# RF-antenna_B.net
KiCad netlist of a schematic drawn in EAGLE
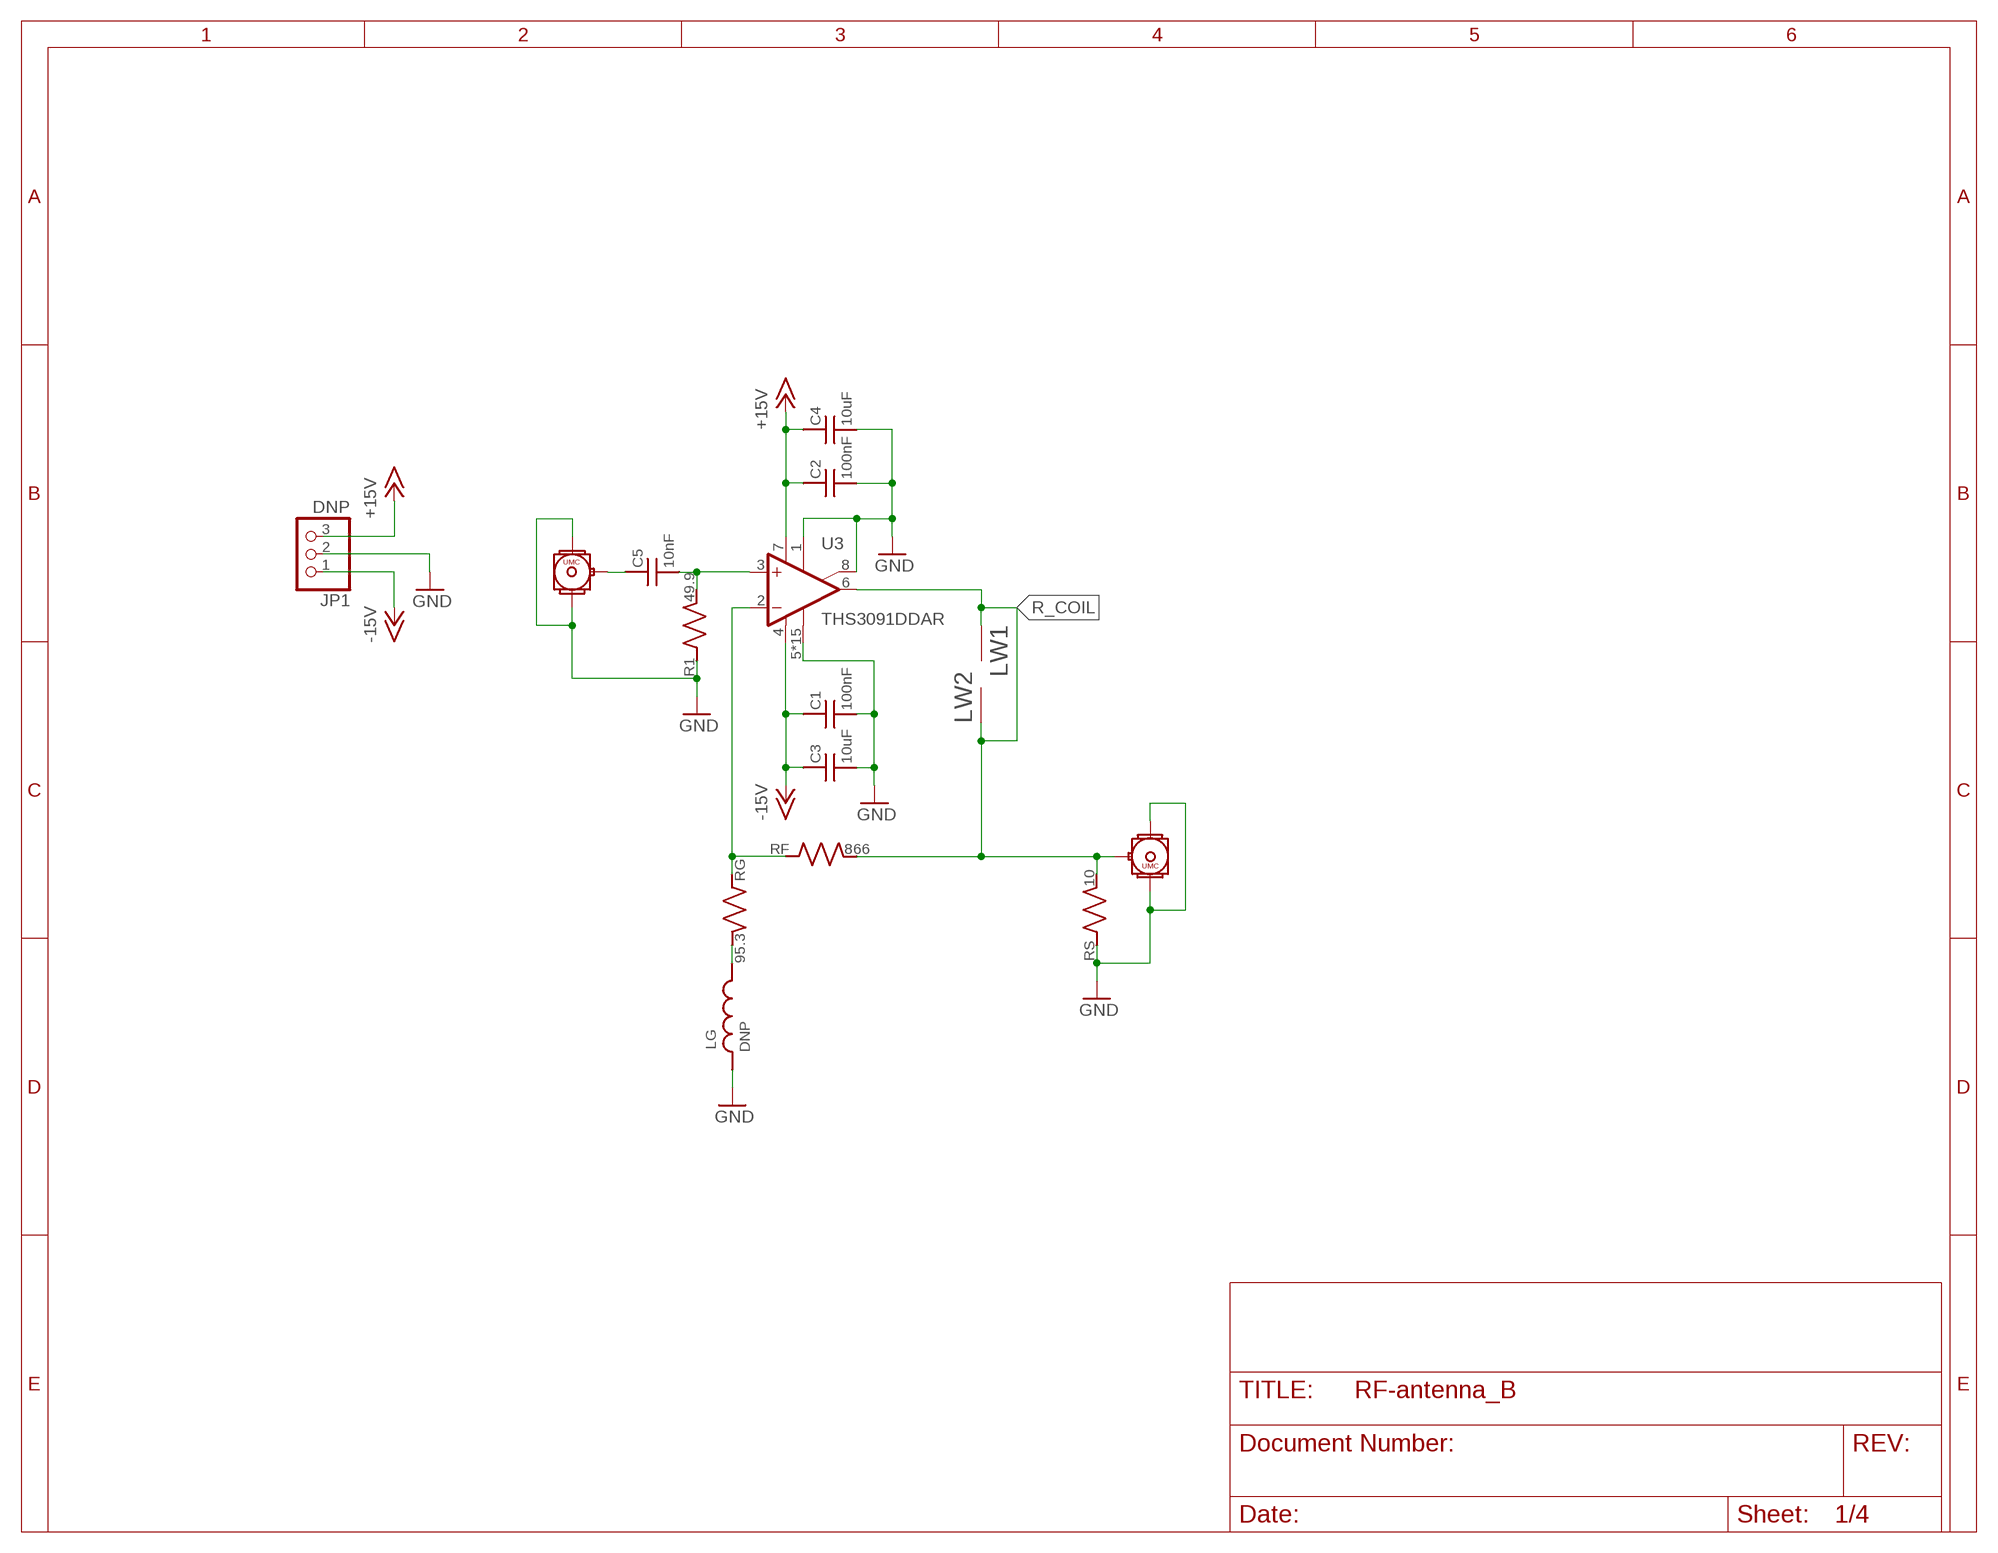
[diagram p0: schematic, sheet 1]
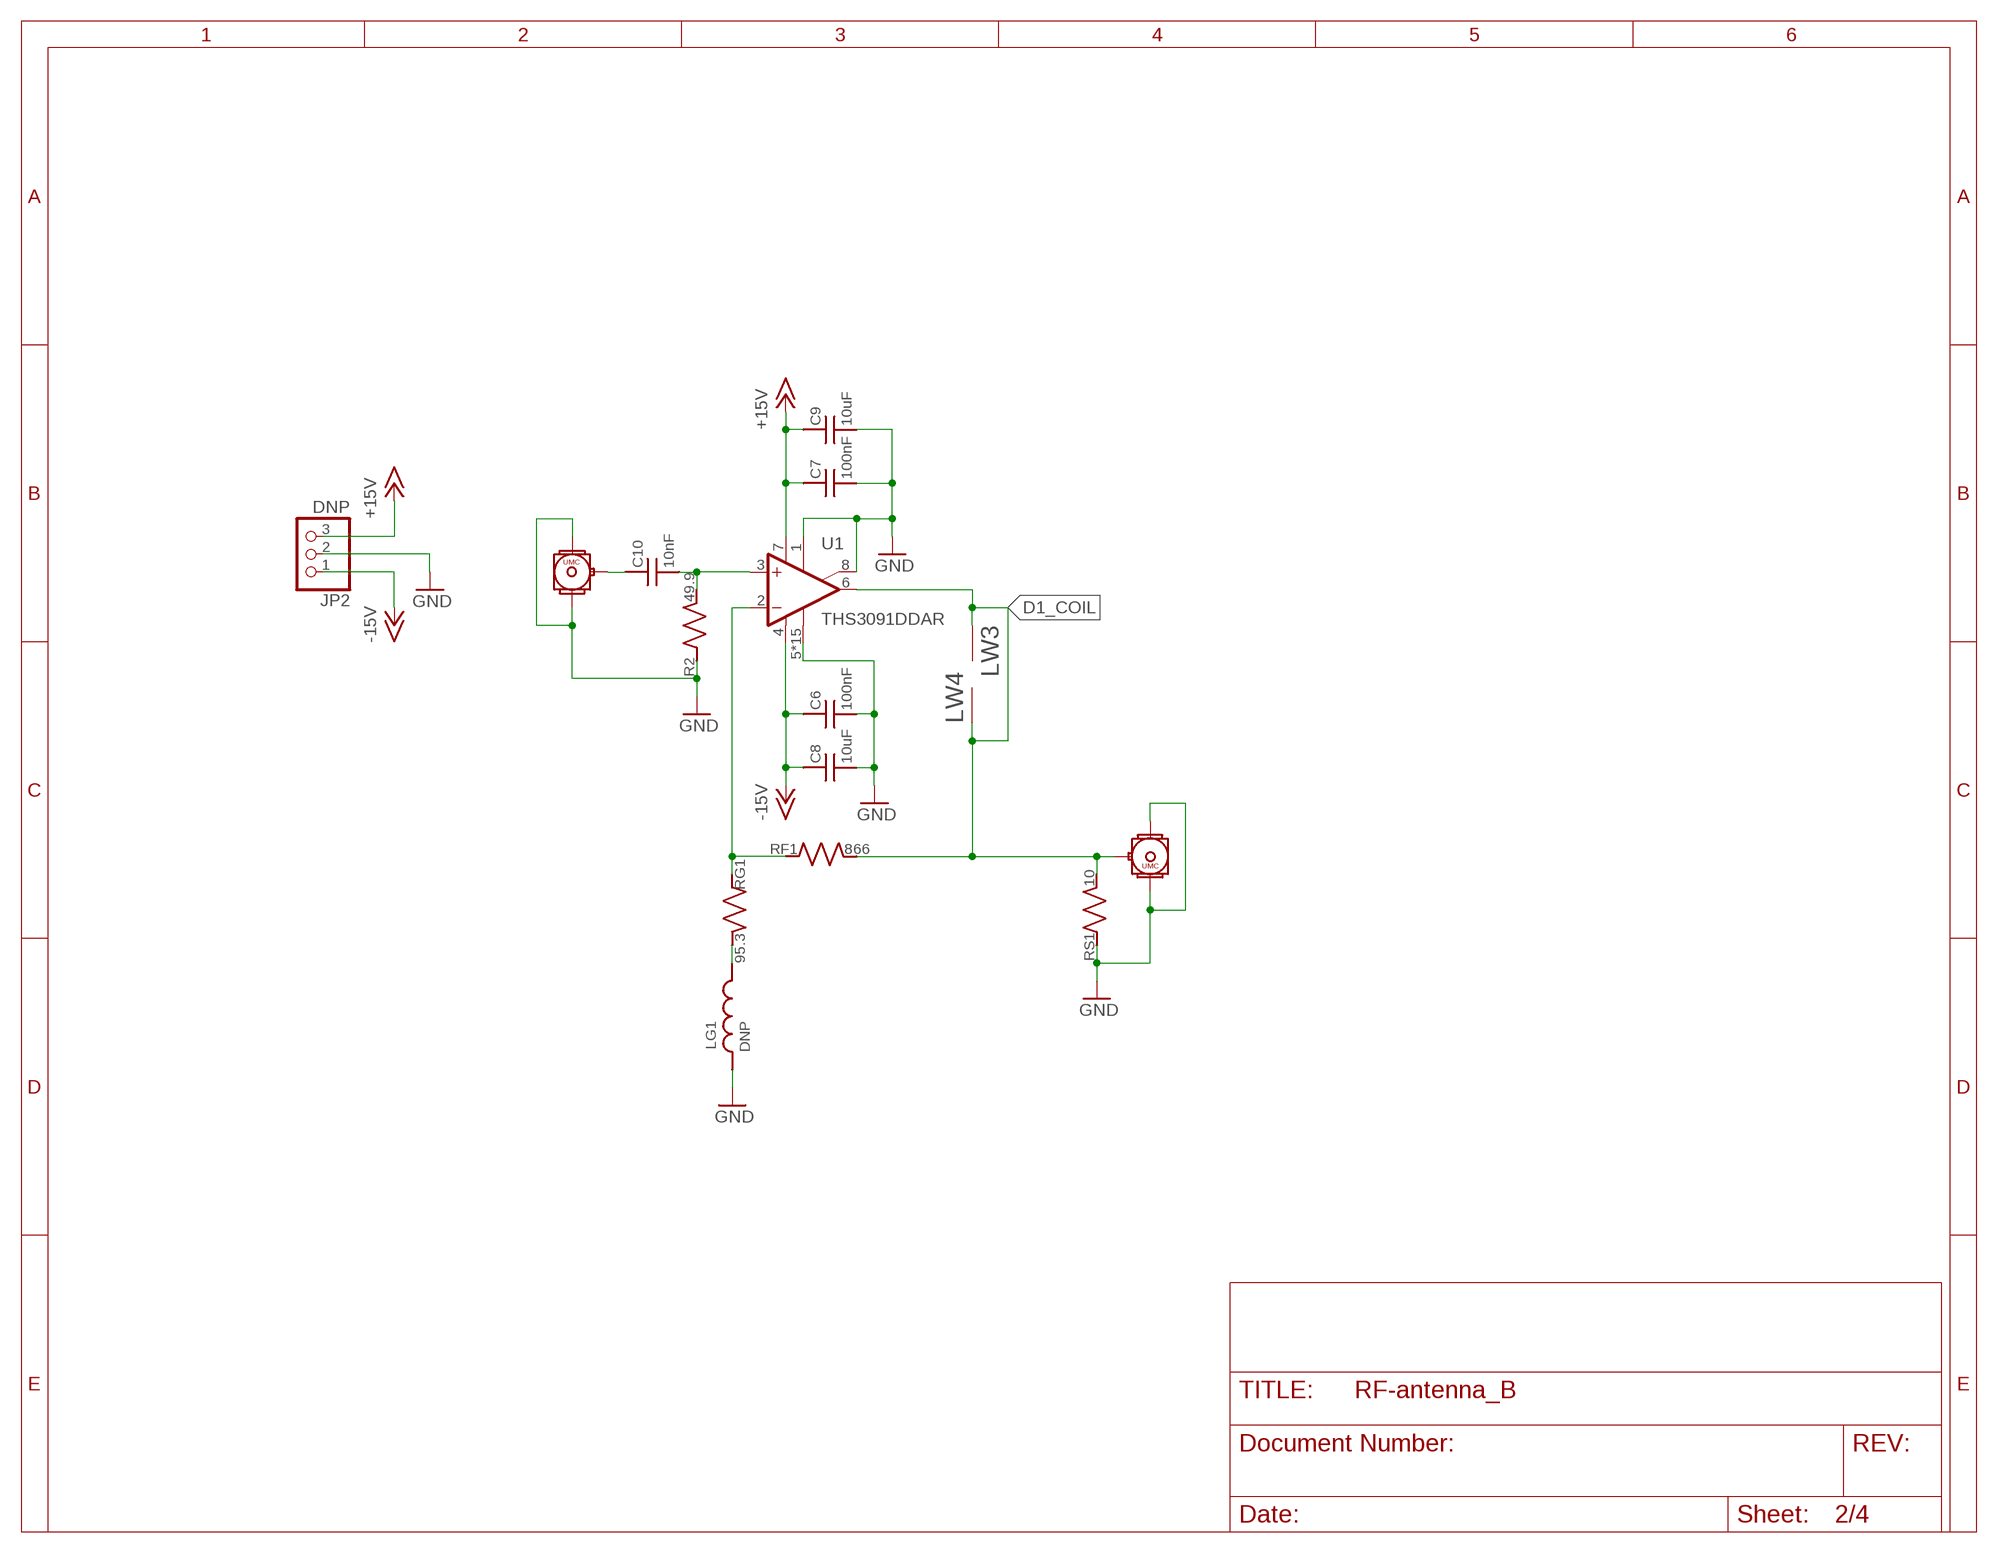
[diagram p1: schematic, sheet 2]
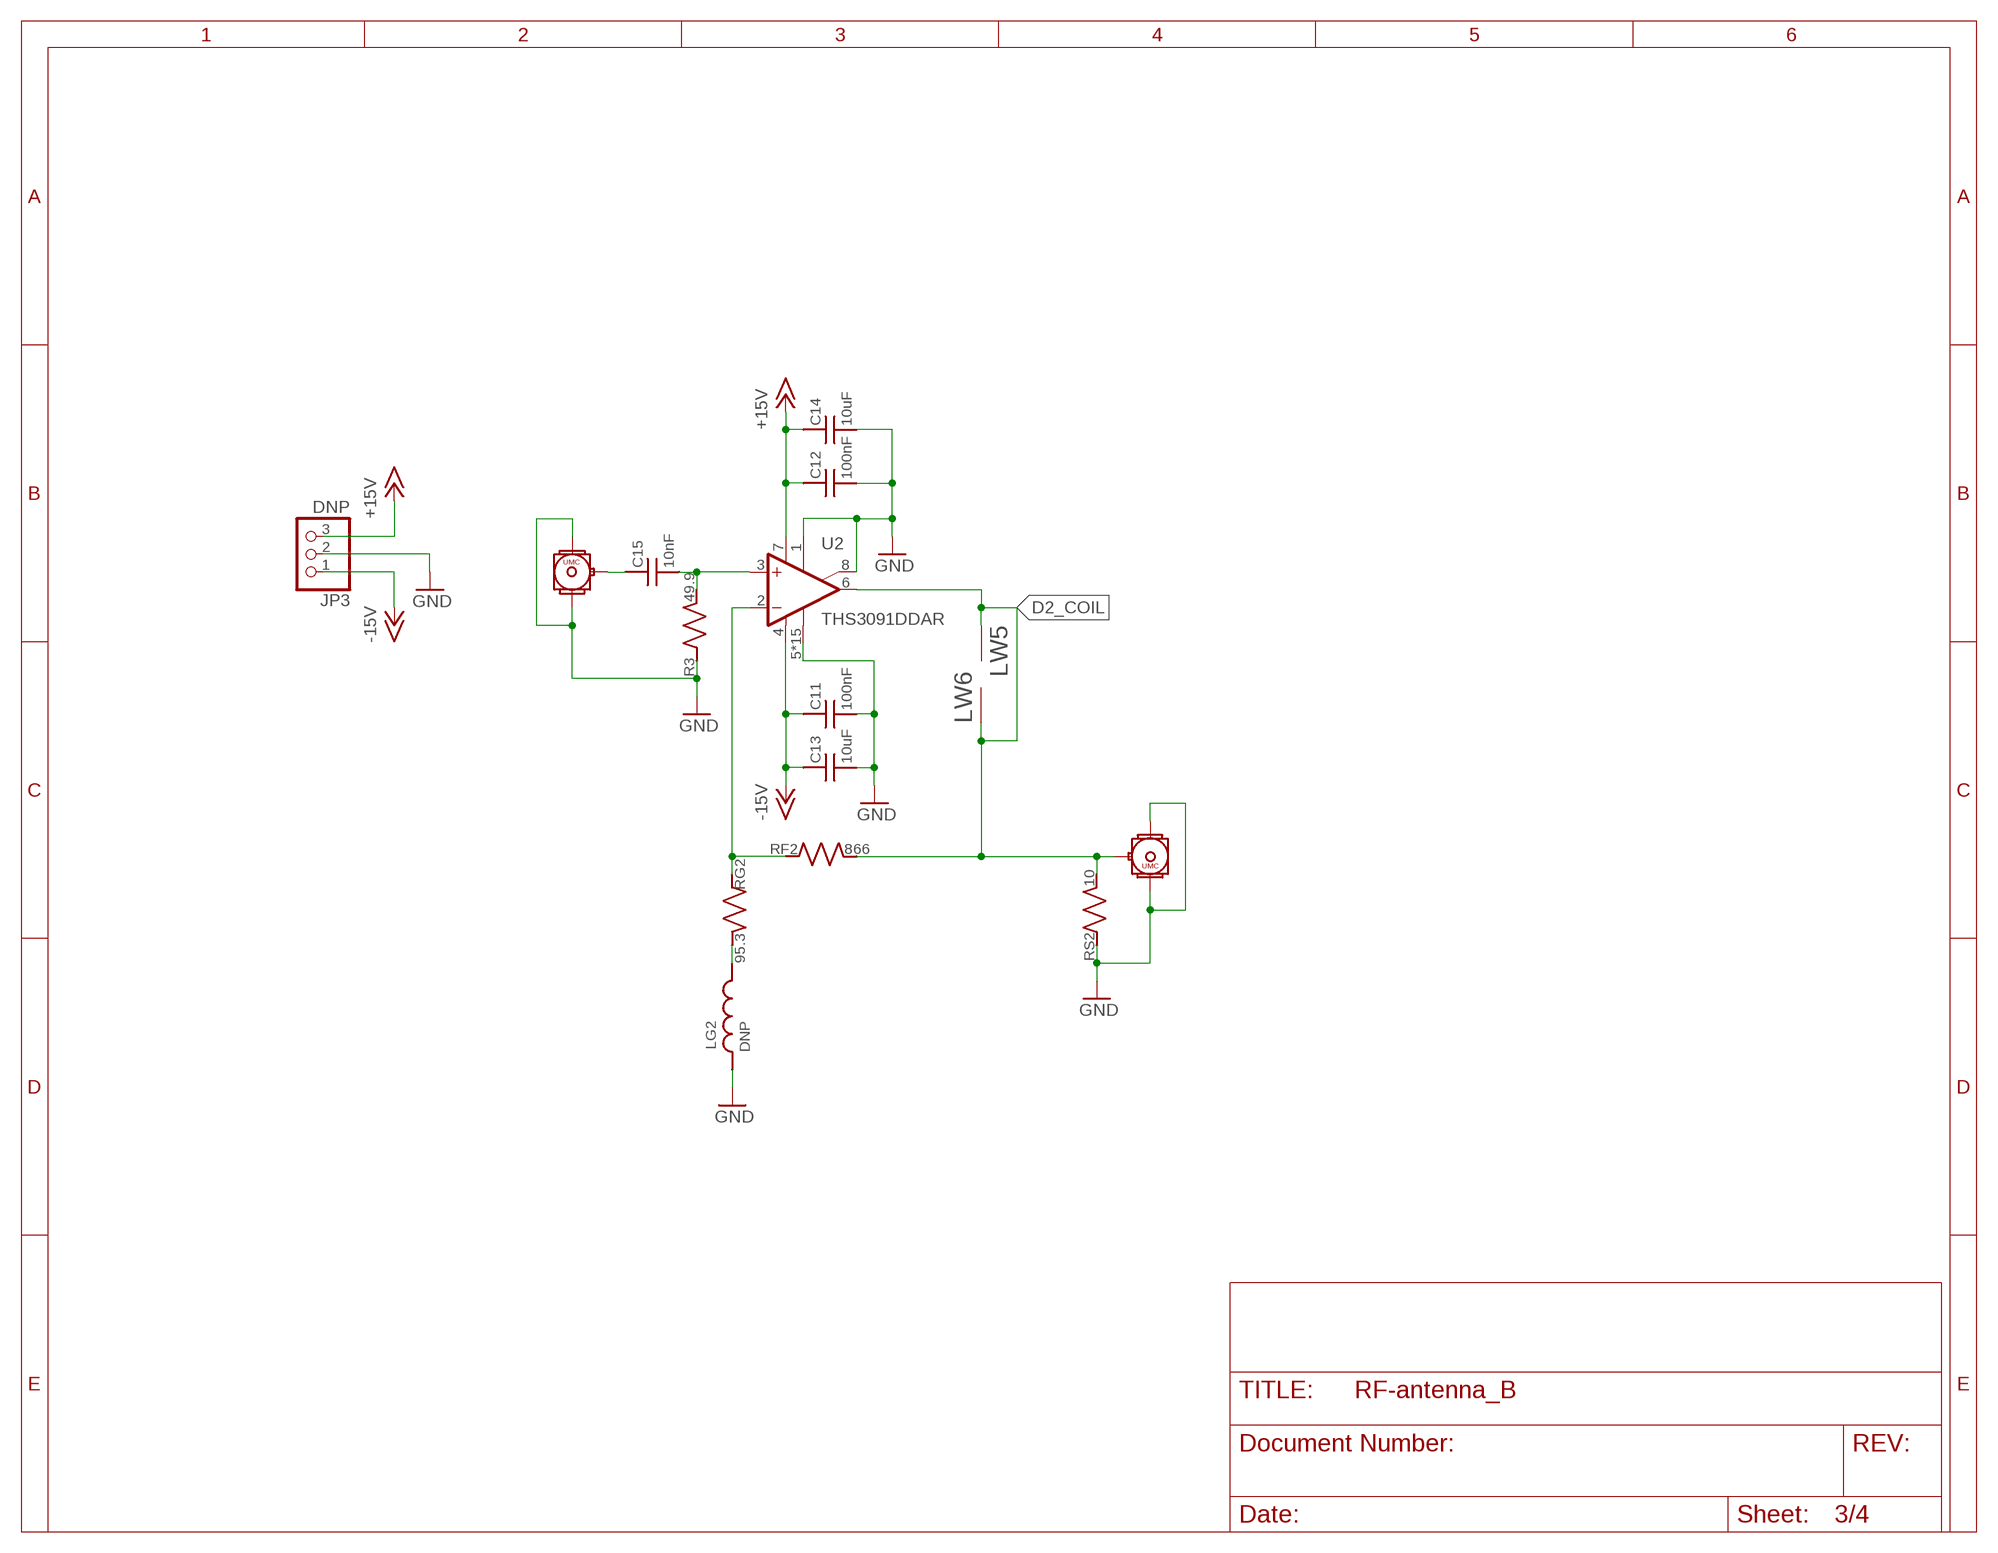
[diagram p2: schematic, sheet 3]
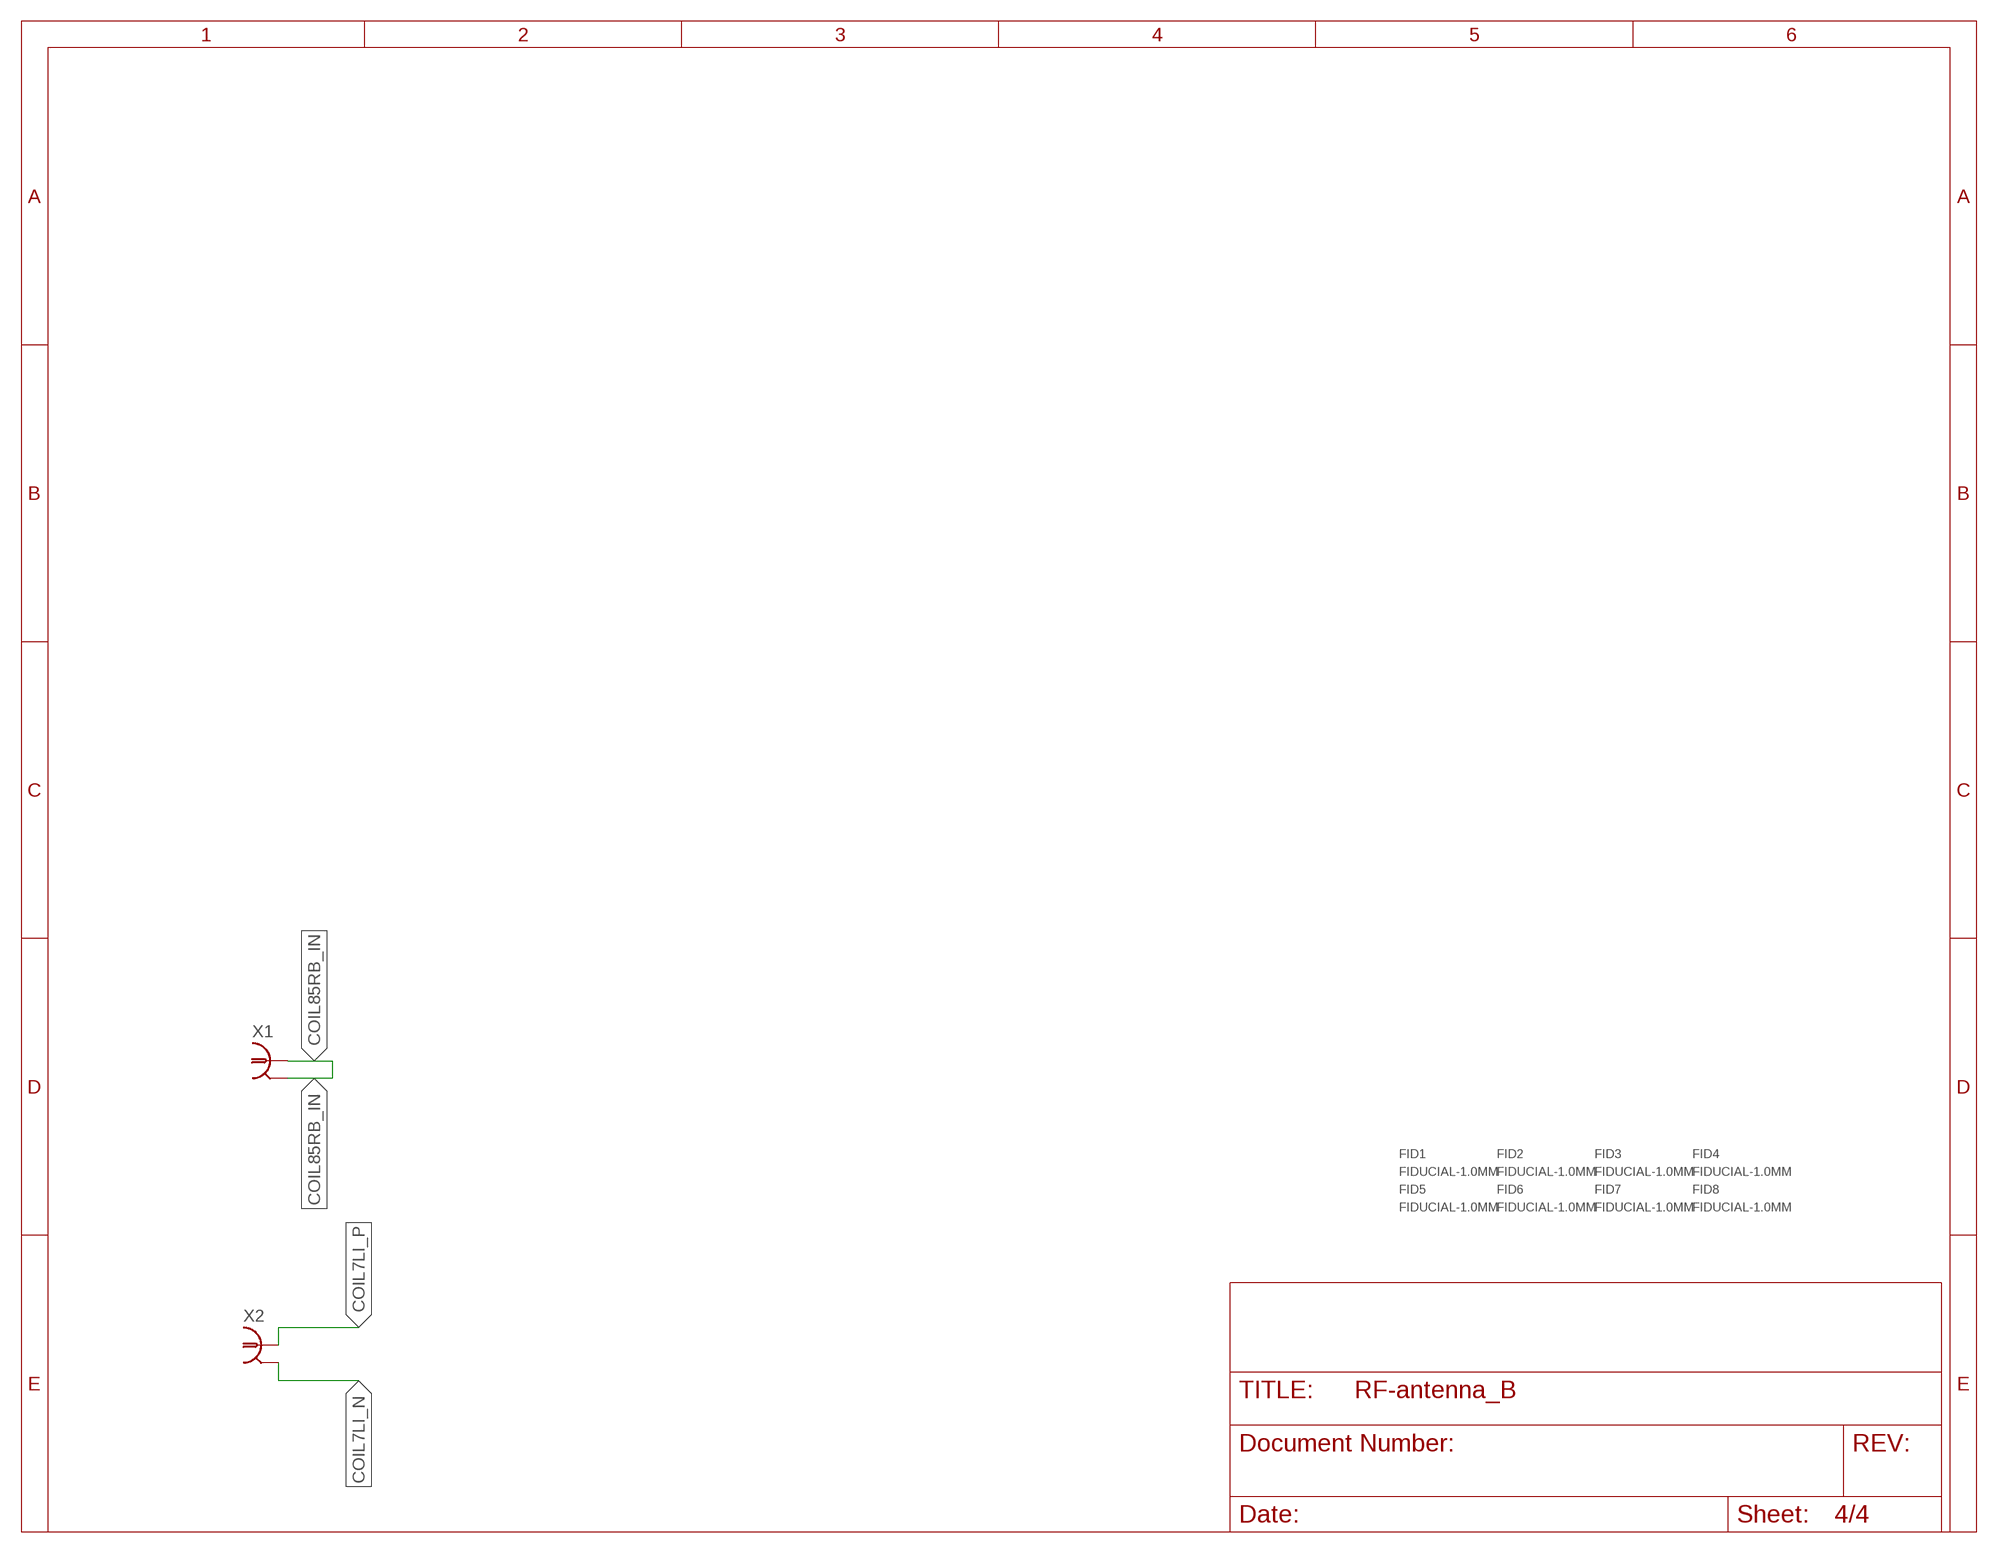
[diagram p3: schematic, sheet 4]

(export (version "E")
  (design (tool "Eeschema 10.0.6"))
  (components
    (comp (ref "C6")
      (value "100nF")
      (footprint "eagle-import:C_MLCC_0603")
      (fields (field (name "PARTNO") "06035C104K4Z2A"))
      (libsource (lib "eagle-import") (part "C_MLCC_SMDCMLCC_0603"))
    )
    (comp (ref "C7")
      (value "100nF")
      (footprint "eagle-import:C_MLCC_0603")
      (fields (field (name "PARTNO") "06035C104K4Z2A"))
      (libsource (lib "eagle-import") (part "C_MLCC_SMDCMLCC_0603"))
    )
    (comp (ref "C8")
      (value "10uF")
      (footprint "eagle-import:C_MLCC_1206")
      (fields (field (name "PARTNO") "C3216X5R1H106K160AB"))
      (libsource (lib "eagle-import") (part "C_MLCC_SMDCMLCC_1206"))
    )
    (comp (ref "C9")
      (value "10uF")
      (footprint "eagle-import:C_MLCC_1206")
      (fields (field (name "PARTNO") "C3216X5R1H106K160AB"))
      (libsource (lib "eagle-import") (part "C_MLCC_SMDCMLCC_1206"))
    )
    (comp (ref "C10")
      (value "10nF")
      (footprint "eagle-import:C_MLCC_0402")
      (fields (field (name "PARTNO") "CL05B103KB5NNNC"))
      (libsource (lib "eagle-import") (part "C_MLCC_SMDCMLCC_0402"))
    )
    (comp (ref "CON3")
      (value "UMC_CONNECTORREGULAR")
      (footprint "eagle-import:UMC_CONNECTOR")
      (fields (field (name "PARTNO") "1909763-1"))
      (libsource (lib "eagle-import") (part "UMC_CONNECTORREGULAR"))
    )
    (comp (ref "CON4")
      (value "UMC_CONNECTORREGULAR")
      (footprint "eagle-import:UMC_CONNECTOR")
      (fields (field (name "PARTNO") "1909763-1"))
      (libsource (lib "eagle-import") (part "UMC_CONNECTORREGULAR"))
    )
    (comp (ref "JP2")
      (value "DNP")
      (footprint "eagle-import:1X03")
      (fields (field (name "PARTNO") "640456-3"))
      (libsource (lib "eagle-import") (part "PINHD-1X3"))
    )
    (comp (ref "LG1")
      (value "DNP")
      (footprint "eagle-import:1008")
      (libsource (lib "eagle-import") (part "L_FERRITE_SMD_1008"))
    )
    (comp (ref "LW3")
      (value "LITZ_TERM")
      (footprint "eagle-import:LITZ_100MHZ")
      (libsource (lib "eagle-import") (part "LITZ_TERM"))
    )
    (comp (ref "LW4")
      (value "LITZ_TERM")
      (footprint "eagle-import:LITZ_100MHZ")
      (libsource (lib "eagle-import") (part "LITZ_TERM"))
    )
    (comp (ref "R2")
      (value "49.9")
      (footprint "eagle-import:R_0402")
      (fields (field (name "PARTNO") "ERA-2AEB49R9X"))
      (libsource (lib "eagle-import") (part "R_SMDR0402"))
    )
    (comp (ref "RF1")
      (value "866")
      (footprint "eagle-import:R_0603")
      (fields (field (name "PARTNO") "ERA-3AEB8660V"))
      (libsource (lib "eagle-import") (part "R_SMDR0603"))
    )
    (comp (ref "RG1")
      (value "95.3")
      (footprint "eagle-import:R_0402")
      (fields (field (name "PARTNO") "ERA-2AEB95R3X"))
      (libsource (lib "eagle-import") (part "R_SMDR0402"))
    )
    (comp (ref "RS1")
      (value "10")
      (footprint "eagle-import:R_1206")
      (fields (field (name "PARTNO") "PHP01206E10R0BST5"))
      (libsource (lib "eagle-import") (part "R_SMDR1206"))
    )
    (comp (ref "U1")
      (value "THS3091DDAR")
      (footprint "eagle-import:DDA8_2P28X2P28")
      (fields (field (name "MANUFACTURER") "Texas Instruments"))
      (libsource (lib "eagle-import") (part "THS3091DDAR"))
    )
    (comp (ref "C11")
      (value "100nF")
      (footprint "eagle-import:C_MLCC_0603")
      (fields (field (name "PARTNO") "06035C104K4Z2A"))
      (libsource (lib "eagle-import") (part "C_MLCC_SMDCMLCC_0603"))
    )
    (comp (ref "C12")
      (value "100nF")
      (footprint "eagle-import:C_MLCC_0603")
      (fields (field (name "PARTNO") "06035C104K4Z2A"))
      (libsource (lib "eagle-import") (part "C_MLCC_SMDCMLCC_0603"))
    )
    (comp (ref "C13")
      (value "10uF")
      (footprint "eagle-import:C_MLCC_1206")
      (fields (field (name "PARTNO") "C3216X5R1H106K160AB"))
      (libsource (lib "eagle-import") (part "C_MLCC_SMDCMLCC_1206"))
    )
    (comp (ref "C14")
      (value "10uF")
      (footprint "eagle-import:C_MLCC_1206")
      (fields (field (name "PARTNO") "C3216X5R1H106K160AB"))
      (libsource (lib "eagle-import") (part "C_MLCC_SMDCMLCC_1206"))
    )
    (comp (ref "C15")
      (value "10nF")
      (footprint "eagle-import:C_MLCC_0402")
      (fields (field (name "PARTNO") "CL05B103KB5NNNC"))
      (libsource (lib "eagle-import") (part "C_MLCC_SMDCMLCC_0402"))
    )
    (comp (ref "CON5")
      (value "UMC_CONNECTORREGULAR")
      (footprint "eagle-import:UMC_CONNECTOR")
      (fields (field (name "PARTNO") "1909763-1"))
      (libsource (lib "eagle-import") (part "UMC_CONNECTORREGULAR"))
    )
    (comp (ref "CON6")
      (value "UMC_CONNECTORREGULAR")
      (footprint "eagle-import:UMC_CONNECTOR")
      (fields (field (name "PARTNO") "1909763-1"))
      (libsource (lib "eagle-import") (part "UMC_CONNECTORREGULAR"))
    )
    (comp (ref "JP3")
      (value "DNP")
      (footprint "eagle-import:1X03")
      (fields (field (name "PARTNO") "640456-3"))
      (libsource (lib "eagle-import") (part "PINHD-1X3"))
    )
    (comp (ref "LG2")
      (value "DNP")
      (footprint "eagle-import:1008")
      (libsource (lib "eagle-import") (part "L_FERRITE_SMD_1008"))
    )
    (comp (ref "LW5")
      (value "LITZ_TERM")
      (footprint "eagle-import:LITZ_100MHZ")
      (libsource (lib "eagle-import") (part "LITZ_TERM"))
    )
    (comp (ref "LW6")
      (value "LITZ_TERM")
      (footprint "eagle-import:LITZ_100MHZ")
      (libsource (lib "eagle-import") (part "LITZ_TERM"))
    )
    (comp (ref "R3")
      (value "49.9")
      (footprint "eagle-import:R_0402")
      (fields (field (name "PARTNO") "ERA-2AEB49R9X"))
      (libsource (lib "eagle-import") (part "R_SMDR0402"))
    )
    (comp (ref "RF2")
      (value "866")
      (footprint "eagle-import:R_0603")
      (fields (field (name "PARTNO") "ERA-3AEB8660V"))
      (libsource (lib "eagle-import") (part "R_SMDR0603"))
    )
    (comp (ref "RG2")
      (value "95.3")
      (footprint "eagle-import:R_0402")
      (fields (field (name "PARTNO") "ERA-2AEB95R3X"))
      (libsource (lib "eagle-import") (part "R_SMDR0402"))
    )
    (comp (ref "RS2")
      (value "10")
      (footprint "eagle-import:R_1206")
      (fields (field (name "PARTNO") "PHP01206E10R0BST5"))
      (libsource (lib "eagle-import") (part "R_SMDR1206"))
    )
    (comp (ref "U2")
      (value "THS3091DDAR")
      (footprint "eagle-import:DDA8_2P28X2P28")
      (fields (field (name "MANUFACTURER") "Texas Instruments"))
      (libsource (lib "eagle-import") (part "THS3091DDAR"))
    )
    (comp (ref "C1")
      (value "100nF")
      (footprint "eagle-import:C_MLCC_0603")
      (fields (field (name "PARTNO") "06035C104K4Z2A"))
      (libsource (lib "eagle-import") (part "C_MLCC_SMDCMLCC_0603"))
    )
    (comp (ref "C2")
      (value "100nF")
      (footprint "eagle-import:C_MLCC_0603")
      (fields (field (name "PARTNO") "06035C104K4Z2A"))
      (libsource (lib "eagle-import") (part "C_MLCC_SMDCMLCC_0603"))
    )
    (comp (ref "C3")
      (value "10uF")
      (footprint "eagle-import:C_MLCC_1206")
      (fields (field (name "PARTNO") "C3216X5R1H106K160AB"))
      (libsource (lib "eagle-import") (part "C_MLCC_SMDCMLCC_1206"))
    )
    (comp (ref "C4")
      (value "10uF")
      (footprint "eagle-import:C_MLCC_1206")
      (fields (field (name "PARTNO") "C3216X5R1H106K160AB"))
      (libsource (lib "eagle-import") (part "C_MLCC_SMDCMLCC_1206"))
    )
    (comp (ref "C5")
      (value "10nF")
      (footprint "eagle-import:C_MLCC_0402")
      (fields (field (name "PARTNO") "CL05B103KB5NNNC"))
      (libsource (lib "eagle-import") (part "C_MLCC_SMDCMLCC_0402"))
    )
    (comp (ref "CON1")
      (value "UMC_CONNECTORREGULAR")
      (footprint "eagle-import:UMC_CONNECTOR")
      (fields (field (name "PARTNO") "1909763-1"))
      (libsource (lib "eagle-import") (part "UMC_CONNECTORREGULAR"))
    )
    (comp (ref "CON2")
      (value "UMC_CONNECTORREGULAR")
      (footprint "eagle-import:UMC_CONNECTOR")
      (fields (field (name "PARTNO") "1909763-1"))
      (libsource (lib "eagle-import") (part "UMC_CONNECTORREGULAR"))
    )
    (comp (ref "JP1")
      (value "DNP")
      (footprint "eagle-import:1X03")
      (fields (field (name "PARTNO") "640456-3"))
      (libsource (lib "eagle-import") (part "PINHD-1X3"))
    )
    (comp (ref "LG")
      (value "DNP")
      (footprint "eagle-import:1008")
      (libsource (lib "eagle-import") (part "L_FERRITE_SMD_1008"))
    )
    (comp (ref "LW1")
      (value "LITZ_TERM")
      (footprint "eagle-import:LITZ_100MHZ")
      (libsource (lib "eagle-import") (part "LITZ_TERM"))
    )
    (comp (ref "LW2")
      (value "LITZ_TERM")
      (footprint "eagle-import:LITZ_100MHZ")
      (libsource (lib "eagle-import") (part "LITZ_TERM"))
    )
    (comp (ref "R1")
      (value "49.9")
      (footprint "eagle-import:R_0402")
      (fields (field (name "PARTNO") "ERA-2AEB49R9X"))
      (libsource (lib "eagle-import") (part "R_SMDR0402"))
    )
    (comp (ref "RF")
      (value "866")
      (footprint "eagle-import:R_0603")
      (fields (field (name "PARTNO") "ERA-3AEB8660V"))
      (libsource (lib "eagle-import") (part "R_SMDR0603"))
    )
    (comp (ref "RG")
      (value "95.3")
      (footprint "eagle-import:R_0402")
      (fields (field (name "PARTNO") "ERA-2AEB95R3X"))
      (libsource (lib "eagle-import") (part "R_SMDR0402"))
    )
    (comp (ref "RS")
      (value "10")
      (footprint "eagle-import:R_1206")
      (fields (field (name "PARTNO") "PHP01206E10R0BST5"))
      (libsource (lib "eagle-import") (part "R_SMDR1206"))
    )
    (comp (ref "U3")
      (value "THS3091DDAR")
      (footprint "eagle-import:DDA8_2P28X2P28")
      (fields (field (name "MANUFACTURER") "Texas Instruments"))
      (libsource (lib "eagle-import") (part "THS3091DDAR"))
    )
    (comp (ref "FID1")
      (value "FIDUCIAL-1.0MM")
      (footprint "eagle-import:FID_1.0MM")
      (libsource (lib "eagle-import") (part "FIDUCIAL-1.0MM"))
    )
    (comp (ref "FID2")
      (value "FIDUCIAL-1.0MM")
      (footprint "eagle-import:FID_1.0MM")
      (libsource (lib "eagle-import") (part "FIDUCIAL-1.0MM"))
    )
    (comp (ref "FID3")
      (value "FIDUCIAL-1.0MM")
      (footprint "eagle-import:FID_1.0MM")
      (libsource (lib "eagle-import") (part "FIDUCIAL-1.0MM"))
    )
    (comp (ref "FID4")
      (value "FIDUCIAL-1.0MM")
      (footprint "eagle-import:FID_1.0MM")
      (libsource (lib "eagle-import") (part "FIDUCIAL-1.0MM"))
    )
    (comp (ref "FID5")
      (value "FIDUCIAL-1.0MM")
      (footprint "eagle-import:FID_1.0MM")
      (libsource (lib "eagle-import") (part "FIDUCIAL-1.0MM"))
    )
    (comp (ref "FID6")
      (value "FIDUCIAL-1.0MM")
      (footprint "eagle-import:FID_1.0MM")
      (libsource (lib "eagle-import") (part "FIDUCIAL-1.0MM"))
    )
    (comp (ref "FID7")
      (value "FIDUCIAL-1.0MM")
      (footprint "eagle-import:FID_1.0MM")
      (libsource (lib "eagle-import") (part "FIDUCIAL-1.0MM"))
    )
    (comp (ref "FID8")
      (value "FIDUCIAL-1.0MM")
      (footprint "eagle-import:FID_1.0MM")
      (libsource (lib "eagle-import") (part "FIDUCIAL-1.0MM"))
    )
    (comp (ref "X1")
      (value "SMA-V")
      (footprint "eagle-import:SMA-V")
      (fields (field (name "PARTNO") "5-1814832-1"))
      (libsource (lib "eagle-import") (part "SMA-V"))
    )
    (comp (ref "X2")
      (value "SMA-V")
      (footprint "eagle-import:SMA-V")
      (fields (field (name "PARTNO") "5-1814832-1"))
      (libsource (lib "eagle-import") (part "SMA-V"))
    )
  )
  (nets
    (net (code "1") (name "+15V") (class "Default")
      (node (ref "C12") (pin "P$1") (pinfunction "1_P$1") (pintype "passive"))
      (node (ref "C14") (pin "P$1") (pinfunction "1_P$1") (pintype "passive"))
      (node (ref "C2") (pin "P$1") (pinfunction "1_P$1") (pintype "passive"))
      (node (ref "C4") (pin "P$1") (pinfunction "1_P$1") (pintype "passive"))
      (node (ref "C7") (pin "P$1") (pinfunction "1_P$1") (pintype "passive"))
      (node (ref "C9") (pin "P$1") (pinfunction "1_P$1") (pintype "passive"))
      (node (ref "JP1") (pin "3") (pinfunction "3_3") (pintype "passive"))
      (node (ref "JP2") (pin "3") (pinfunction "3_3") (pintype "passive"))
      (node (ref "JP3") (pin "3") (pinfunction "3_3") (pintype "passive"))
      (node (ref "U1") (pin "7") (pinfunction "V+_7") (pintype "power_in"))
      (node (ref "U2") (pin "7") (pinfunction "V+_7") (pintype "power_in"))
      (node (ref "U3") (pin "7") (pinfunction "V+_7") (pintype "power_in"))
    )
    (net (code "2") (name "-15V") (class "Default")
      (node (ref "C1") (pin "P$1") (pinfunction "1_P$1") (pintype "passive"))
      (node (ref "C11") (pin "P$1") (pinfunction "1_P$1") (pintype "passive"))
      (node (ref "C13") (pin "P$1") (pinfunction "1_P$1") (pintype "passive"))
      (node (ref "C3") (pin "P$1") (pinfunction "1_P$1") (pintype "passive"))
      (node (ref "C6") (pin "P$1") (pinfunction "1_P$1") (pintype "passive"))
      (node (ref "C8") (pin "P$1") (pinfunction "1_P$1") (pintype "passive"))
      (node (ref "JP1") (pin "1") (pinfunction "1_1") (pintype "passive"))
      (node (ref "JP2") (pin "1") (pinfunction "1_1") (pintype "passive"))
      (node (ref "JP3") (pin "1") (pinfunction "1_1") (pintype "passive"))
      (node (ref "U1") (pin "4") (pinfunction "V-_4") (pintype "power_in"))
      (node (ref "U2") (pin "4") (pinfunction "V-_4") (pintype "power_in"))
      (node (ref "U3") (pin "4") (pinfunction "V-_4") (pintype "power_in"))
    )
    (net (code "3") (name "COIL7LI_N") (class "Default")
      (node (ref "X2") (pin "GND1") (pinfunction "2_GND1") (pintype "passive"))
      (node (ref "X2") (pin "GND2") (pinfunction "2_GND2") (pintype "passive"))
      (node (ref "X2") (pin "GND3") (pinfunction "2_GND3") (pintype "passive"))
      (node (ref "X2") (pin "GND4") (pinfunction "2_GND4") (pintype "passive"))
    )
    (net (code "4") (name "COIL7LI_P") (class "Default")
      (node (ref "X2") (pin "RF") (pinfunction "1_RF") (pintype "passive"))
    )
    (net (code "5") (name "COIL85RB_IN") (class "Default")
      (node (ref "X1") (pin "GND1") (pinfunction "2_GND1") (pintype "passive"))
      (node (ref "X1") (pin "GND2") (pinfunction "2_GND2") (pintype "passive"))
      (node (ref "X1") (pin "GND3") (pinfunction "2_GND3") (pintype "passive"))
      (node (ref "X1") (pin "GND4") (pinfunction "2_GND4") (pintype "passive"))
      (node (ref "X1") (pin "RF") (pinfunction "1_RF") (pintype "passive"))
    )
    (net (code "6") (name "D1_COIL") (class "Default")
      (node (ref "CON4") (pin "P$1") (pinfunction "P$1_P$1") (pintype "bidirectional"))
      (node (ref "LW3") (pin "T1") (pinfunction "P1_T1") (pintype "passive"))
      (node (ref "LW4") (pin "T1") (pinfunction "P1_T1") (pintype "passive"))
      (node (ref "RF1") (pin "P$2") (pinfunction "2_P$2") (pintype "passive"))
      (node (ref "RS1") (pin "P$2") (pinfunction "2_P$2") (pintype "passive"))
      (node (ref "U1") (pin "6") (pinfunction "OUT_6") (pintype "output"))
    )
    (net (code "7") (name "D2_COIL") (class "Default")
      (node (ref "CON6") (pin "P$1") (pinfunction "P$1_P$1") (pintype "bidirectional"))
      (node (ref "LW5") (pin "T1") (pinfunction "P1_T1") (pintype "passive"))
      (node (ref "LW6") (pin "T1") (pinfunction "P1_T1") (pintype "passive"))
      (node (ref "RF2") (pin "P$2") (pinfunction "2_P$2") (pintype "passive"))
      (node (ref "RS2") (pin "P$2") (pinfunction "2_P$2") (pintype "passive"))
      (node (ref "U2") (pin "6") (pinfunction "OUT_6") (pintype "output"))
    )
    (net (code "8") (name "GND") (class "Default")
      (node (ref "C1") (pin "P$2") (pinfunction "2_P$2") (pintype "passive"))
      (node (ref "C11") (pin "P$2") (pinfunction "2_P$2") (pintype "passive"))
      (node (ref "C12") (pin "P$2") (pinfunction "2_P$2") (pintype "passive"))
      (node (ref "C13") (pin "P$2") (pinfunction "2_P$2") (pintype "passive"))
      (node (ref "C14") (pin "P$2") (pinfunction "2_P$2") (pintype "passive"))
      (node (ref "C2") (pin "P$2") (pinfunction "2_P$2") (pintype "passive"))
      (node (ref "C3") (pin "P$2") (pinfunction "2_P$2") (pintype "passive"))
      (node (ref "C4") (pin "P$2") (pinfunction "2_P$2") (pintype "passive"))
      (node (ref "C6") (pin "P$2") (pinfunction "2_P$2") (pintype "passive"))
      (node (ref "C7") (pin "P$2") (pinfunction "2_P$2") (pintype "passive"))
      (node (ref "C8") (pin "P$2") (pinfunction "2_P$2") (pintype "passive"))
      (node (ref "C9") (pin "P$2") (pinfunction "2_P$2") (pintype "passive"))
      (node (ref "CON1") (pin "P$2") (pinfunction "P$2_P$2") (pintype "bidirectional"))
      (node (ref "CON1") (pin "P$3") (pinfunction "P$3_P$3") (pintype "bidirectional"))
      (node (ref "CON2") (pin "P$2") (pinfunction "P$2_P$2") (pintype "bidirectional"))
      (node (ref "CON2") (pin "P$3") (pinfunction "P$3_P$3") (pintype "bidirectional"))
      (node (ref "CON3") (pin "P$2") (pinfunction "P$2_P$2") (pintype "bidirectional"))
      (node (ref "CON3") (pin "P$3") (pinfunction "P$3_P$3") (pintype "bidirectional"))
      (node (ref "CON4") (pin "P$2") (pinfunction "P$2_P$2") (pintype "bidirectional"))
      (node (ref "CON4") (pin "P$3") (pinfunction "P$3_P$3") (pintype "bidirectional"))
      (node (ref "CON5") (pin "P$2") (pinfunction "P$2_P$2") (pintype "bidirectional"))
      (node (ref "CON5") (pin "P$3") (pinfunction "P$3_P$3") (pintype "bidirectional"))
      (node (ref "CON6") (pin "P$2") (pinfunction "P$2_P$2") (pintype "bidirectional"))
      (node (ref "CON6") (pin "P$3") (pinfunction "P$3_P$3") (pintype "bidirectional"))
      (node (ref "JP1") (pin "2") (pinfunction "2_2") (pintype "passive"))
      (node (ref "JP2") (pin "2") (pinfunction "2_2") (pintype "passive"))
      (node (ref "JP3") (pin "2") (pinfunction "2_2") (pintype "passive"))
      (node (ref "LG") (pin "P$1") (pinfunction "1_P$1") (pintype "passive"))
      (node (ref "LG1") (pin "P$1") (pinfunction "1_P$1") (pintype "passive"))
      (node (ref "LG2") (pin "P$1") (pinfunction "1_P$1") (pintype "passive"))
      (node (ref "R1") (pin "P$1") (pinfunction "1_P$1") (pintype "passive"))
      (node (ref "R2") (pin "P$1") (pinfunction "1_P$1") (pintype "passive"))
      (node (ref "R3") (pin "P$1") (pinfunction "1_P$1") (pintype "passive"))
      (node (ref "RS") (pin "P$1") (pinfunction "1_P$1") (pintype "passive"))
      (node (ref "RS1") (pin "P$1") (pinfunction "1_P$1") (pintype "passive"))
      (node (ref "RS2") (pin "P$1") (pinfunction "1_P$1") (pintype "passive"))
      (node (ref "U1") (pin "1") (pinfunction "ON1_1") (pintype "passive"))
      (node (ref "U1") (pin "5") (pinfunction "OPT_5") (pintype "passive"))
      (node (ref "U1") (pin "8") (pinfunction "ON2_8") (pintype "passive"))
      (node (ref "U1") (pin "EPAD") (pinfunction "OPT_EPAD") (pintype "passive"))
      (node (ref "U1") (pin "P$1") (pinfunction "OPT_P$1") (pintype "passive"))
      (node (ref "U1") (pin "P$10") (pinfunction "OPT_P$10") (pintype "passive"))
      (node (ref "U1") (pin "P$11") (pinfunction "OPT_P$11") (pintype "passive"))
      (node (ref "U1") (pin "P$12") (pinfunction "OPT_P$12") (pintype "passive"))
      (node (ref "U1") (pin "P$13") (pinfunction "OPT_P$13") (pintype "passive"))
      (node (ref "U1") (pin "P$2") (pinfunction "OPT_P$2") (pintype "passive"))
      (node (ref "U1") (pin "P$3") (pinfunction "OPT_P$3") (pintype "passive"))
      (node (ref "U1") (pin "P$4") (pinfunction "OPT_P$4") (pintype "passive"))
      (node (ref "U1") (pin "P$5") (pinfunction "OPT_P$5") (pintype "passive"))
      (node (ref "U1") (pin "P$6") (pinfunction "OPT_P$6") (pintype "passive"))
      (node (ref "U1") (pin "P$7") (pinfunction "OPT_P$7") (pintype "passive"))
      (node (ref "U1") (pin "P$8") (pinfunction "OPT_P$8") (pintype "passive"))
      (node (ref "U1") (pin "P$9") (pinfunction "OPT_P$9") (pintype "passive"))
      (node (ref "U2") (pin "1") (pinfunction "ON1_1") (pintype "passive"))
      (node (ref "U2") (pin "5") (pinfunction "OPT_5") (pintype "passive"))
      (node (ref "U2") (pin "8") (pinfunction "ON2_8") (pintype "passive"))
      (node (ref "U2") (pin "EPAD") (pinfunction "OPT_EPAD") (pintype "passive"))
      (node (ref "U2") (pin "P$1") (pinfunction "OPT_P$1") (pintype "passive"))
      (node (ref "U2") (pin "P$10") (pinfunction "OPT_P$10") (pintype "passive"))
      (node (ref "U2") (pin "P$11") (pinfunction "OPT_P$11") (pintype "passive"))
      (node (ref "U2") (pin "P$12") (pinfunction "OPT_P$12") (pintype "passive"))
      (node (ref "U2") (pin "P$13") (pinfunction "OPT_P$13") (pintype "passive"))
      (node (ref "U2") (pin "P$2") (pinfunction "OPT_P$2") (pintype "passive"))
      (node (ref "U2") (pin "P$3") (pinfunction "OPT_P$3") (pintype "passive"))
      (node (ref "U2") (pin "P$4") (pinfunction "OPT_P$4") (pintype "passive"))
      (node (ref "U2") (pin "P$5") (pinfunction "OPT_P$5") (pintype "passive"))
      (node (ref "U2") (pin "P$6") (pinfunction "OPT_P$6") (pintype "passive"))
      (node (ref "U2") (pin "P$7") (pinfunction "OPT_P$7") (pintype "passive"))
      (node (ref "U2") (pin "P$8") (pinfunction "OPT_P$8") (pintype "passive"))
      (node (ref "U2") (pin "P$9") (pinfunction "OPT_P$9") (pintype "passive"))
      (node (ref "U3") (pin "1") (pinfunction "ON1_1") (pintype "passive"))
      (node (ref "U3") (pin "5") (pinfunction "OPT_5") (pintype "passive"))
      (node (ref "U3") (pin "8") (pinfunction "ON2_8") (pintype "passive"))
      (node (ref "U3") (pin "EPAD") (pinfunction "OPT_EPAD") (pintype "passive"))
      (node (ref "U3") (pin "P$1") (pinfunction "OPT_P$1") (pintype "passive"))
      (node (ref "U3") (pin "P$10") (pinfunction "OPT_P$10") (pintype "passive"))
      (node (ref "U3") (pin "P$11") (pinfunction "OPT_P$11") (pintype "passive"))
      (node (ref "U3") (pin "P$12") (pinfunction "OPT_P$12") (pintype "passive"))
      (node (ref "U3") (pin "P$13") (pinfunction "OPT_P$13") (pintype "passive"))
      (node (ref "U3") (pin "P$2") (pinfunction "OPT_P$2") (pintype "passive"))
      (node (ref "U3") (pin "P$3") (pinfunction "OPT_P$3") (pintype "passive"))
      (node (ref "U3") (pin "P$4") (pinfunction "OPT_P$4") (pintype "passive"))
      (node (ref "U3") (pin "P$5") (pinfunction "OPT_P$5") (pintype "passive"))
      (node (ref "U3") (pin "P$6") (pinfunction "OPT_P$6") (pintype "passive"))
      (node (ref "U3") (pin "P$7") (pinfunction "OPT_P$7") (pintype "passive"))
      (node (ref "U3") (pin "P$8") (pinfunction "OPT_P$8") (pintype "passive"))
      (node (ref "U3") (pin "P$9") (pinfunction "OPT_P$9") (pintype "passive"))
    )
    (net (code "9") (name "Net-(C5-1)") (class "Default")
      (node (ref "C5") (pin "P$1") (pinfunction "1_P$1") (pintype "passive"))
      (node (ref "CON2") (pin "P$1") (pinfunction "P$1_P$1") (pintype "bidirectional"))
    )
    (net (code "10") (name "Net-(C5-2)") (class "Default")
      (node (ref "C5") (pin "P$2") (pinfunction "2_P$2") (pintype "passive"))
      (node (ref "R1") (pin "P$2") (pinfunction "2_P$2") (pintype "passive"))
      (node (ref "U3") (pin "3") (pinfunction "+IN_3") (pintype "input"))
    )
    (net (code "11") (name "Net-(C10-1)") (class "Default")
      (node (ref "C10") (pin "P$1") (pinfunction "1_P$1") (pintype "passive"))
      (node (ref "CON3") (pin "P$1") (pinfunction "P$1_P$1") (pintype "bidirectional"))
    )
    (net (code "12") (name "Net-(C10-2)") (class "Default")
      (node (ref "C10") (pin "P$2") (pinfunction "2_P$2") (pintype "passive"))
      (node (ref "R2") (pin "P$2") (pinfunction "2_P$2") (pintype "passive"))
      (node (ref "U1") (pin "3") (pinfunction "+IN_3") (pintype "input"))
    )
    (net (code "13") (name "Net-(C15-1)") (class "Default")
      (node (ref "C15") (pin "P$1") (pinfunction "1_P$1") (pintype "passive"))
      (node (ref "CON5") (pin "P$1") (pinfunction "P$1_P$1") (pintype "bidirectional"))
    )
    (net (code "14") (name "Net-(C15-2)") (class "Default")
      (node (ref "C15") (pin "P$2") (pinfunction "2_P$2") (pintype "passive"))
      (node (ref "R3") (pin "P$2") (pinfunction "2_P$2") (pintype "passive"))
      (node (ref "U2") (pin "3") (pinfunction "+IN_3") (pintype "input"))
    )
    (net (code "15") (name "Net-(LG-2)") (class "Default")
      (node (ref "LG") (pin "P$2") (pinfunction "2_P$2") (pintype "passive"))
      (node (ref "RG") (pin "P$2") (pinfunction "2_P$2") (pintype "passive"))
    )
    (net (code "16") (name "Net-(LG1-2)") (class "Default")
      (node (ref "LG1") (pin "P$2") (pinfunction "2_P$2") (pintype "passive"))
      (node (ref "RG1") (pin "P$2") (pinfunction "2_P$2") (pintype "passive"))
    )
    (net (code "17") (name "Net-(LG2-2)") (class "Default")
      (node (ref "LG2") (pin "P$2") (pinfunction "2_P$2") (pintype "passive"))
      (node (ref "RG2") (pin "P$2") (pinfunction "2_P$2") (pintype "passive"))
    )
    (net (code "18") (name "Net-(RF-1)") (class "Default")
      (node (ref "RF") (pin "P$1") (pinfunction "1_P$1") (pintype "passive"))
      (node (ref "RG") (pin "P$1") (pinfunction "1_P$1") (pintype "passive"))
      (node (ref "U3") (pin "2") (pinfunction "-IN_2") (pintype "input"))
    )
    (net (code "19") (name "Net-(RF1-1)") (class "Default")
      (node (ref "RF1") (pin "P$1") (pinfunction "1_P$1") (pintype "passive"))
      (node (ref "RG1") (pin "P$1") (pinfunction "1_P$1") (pintype "passive"))
      (node (ref "U1") (pin "2") (pinfunction "-IN_2") (pintype "input"))
    )
    (net (code "20") (name "Net-(RF2-1)") (class "Default")
      (node (ref "RF2") (pin "P$1") (pinfunction "1_P$1") (pintype "passive"))
      (node (ref "RG2") (pin "P$1") (pinfunction "1_P$1") (pintype "passive"))
      (node (ref "U2") (pin "2") (pinfunction "-IN_2") (pintype "input"))
    )
    (net (code "21") (name "R_COIL") (class "Default")
      (node (ref "CON1") (pin "P$1") (pinfunction "P$1_P$1") (pintype "bidirectional"))
      (node (ref "LW1") (pin "T1") (pinfunction "P1_T1") (pintype "passive"))
      (node (ref "LW2") (pin "T1") (pinfunction "P1_T1") (pintype "passive"))
      (node (ref "RF") (pin "P$2") (pinfunction "2_P$2") (pintype "passive"))
      (node (ref "RS") (pin "P$2") (pinfunction "2_P$2") (pintype "passive"))
      (node (ref "U3") (pin "6") (pinfunction "OUT_6") (pintype "output"))
    )
  )
)
